# FAT93.net
KiCad netlist of a schematic drawn in Altium Designer
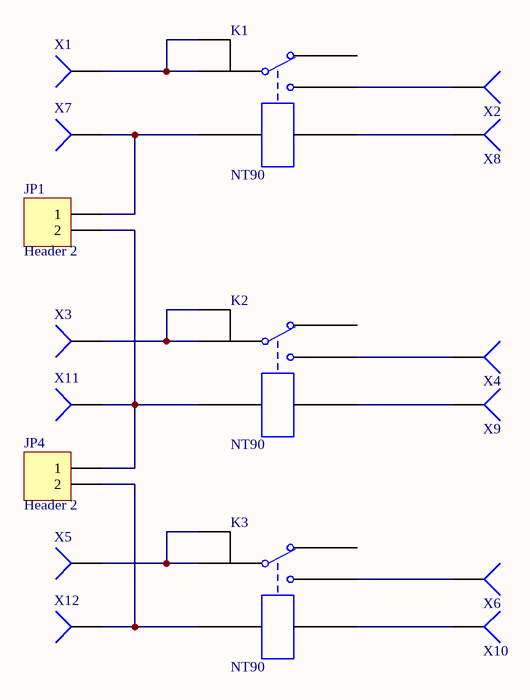
[diagram p0: FAT93.SchDoc]

(export (version "E")
  (design (tool "Eeschema 10.0.6"))
  (components
    (comp (ref "JP1")
      (value "Header 2")
      (footprint "2EDGR-5.0-2P")
      (description "Header, 2-Pin")
      (fields (field (name "MANUFACTURER") "Generic Components") (field (name "PUBLISHER") "Altium Limited"))
      (libsource (lib "Miscellaneous Connectors") (part "Header 2"))
    )
    (comp (ref "JP4")
      (value "Header 2")
      (footprint "2EDGR-5.0-2P")
      (description "Header, 2-Pin")
      (fields (field (name "MANUFACTURER") "Generic Components") (field (name "PUBLISHER") "Altium Limited"))
      (libsource (lib "Miscellaneous Connectors") (part "Header 2"))
    )
    (comp (ref "K1")
      (value "NT90")
      (footprint "NT90")
      (description "Single-Pole Dual-Throw Relay")
      (fields (field (name "MANUFACTURER") "Generic Components") (field (name "PUBLISHER") "Altium Limited"))
      (libsource (lib "PAL") (part "NT90"))
    )
    (comp (ref "K2")
      (value "NT90")
      (footprint "NT90")
      (description "Single-Pole Dual-Throw Relay")
      (fields (field (name "MANUFACTURER") "Generic Components") (field (name "PUBLISHER") "Altium Limited"))
      (libsource (lib "PAL") (part "NT90"))
    )
    (comp (ref "K3")
      (value "NT90")
      (footprint "NT90")
      (description "Single-Pole Dual-Throw Relay")
      (fields (field (name "MANUFACTURER") "Generic Components") (field (name "PUBLISHER") "Altium Limited"))
      (libsource (lib "PAL") (part "NT90"))
    )
    (comp (ref "X1")
      (value "Socket")
      (footprint "k13-4-9")
      (fields (field (name "MANUFACTURER") "Generic Components") (field (name "PUBLISHER") "Altium Limited"))
      (libsource (lib "Miscellaneous Connectors") (part "Socket"))
    )
    (comp (ref "X2")
      (value "Socket")
      (footprint "k13-4-9")
      (fields (field (name "MANUFACTURER") "Generic Components") (field (name "PUBLISHER") "Altium Limited"))
      (libsource (lib "Miscellaneous Connectors") (part "Socket"))
    )
    (comp (ref "X3")
      (value "Socket")
      (footprint "k13-4-9")
      (fields (field (name "MANUFACTURER") "Generic Components") (field (name "PUBLISHER") "Altium Limited"))
      (libsource (lib "Miscellaneous Connectors") (part "Socket"))
    )
    (comp (ref "X4")
      (value "Socket")
      (footprint "k13-4-9")
      (fields (field (name "MANUFACTURER") "Generic Components") (field (name "PUBLISHER") "Altium Limited"))
      (libsource (lib "Miscellaneous Connectors") (part "Socket"))
    )
    (comp (ref "X5")
      (value "Socket")
      (footprint "k13-4-9")
      (fields (field (name "MANUFACTURER") "Generic Components") (field (name "PUBLISHER") "Altium Limited"))
      (libsource (lib "Miscellaneous Connectors") (part "Socket"))
    )
    (comp (ref "X6")
      (value "Socket")
      (footprint "k13-4-9")
      (fields (field (name "MANUFACTURER") "Generic Components") (field (name "PUBLISHER") "Altium Limited"))
      (libsource (lib "Miscellaneous Connectors") (part "Socket"))
    )
    (comp (ref "X7")
      (value "Socket")
      (footprint "DJ610A-4.8")
      (fields (field (name "MANUFACTURER") "Generic Components") (field (name "PUBLISHER") "Altium Limited"))
      (libsource (lib "Miscellaneous Connectors") (part "Socket"))
    )
    (comp (ref "X8")
      (value "Socket")
      (footprint "DJ610A-4.8")
      (fields (field (name "MANUFACTURER") "Generic Components") (field (name "PUBLISHER") "Altium Limited"))
      (libsource (lib "Miscellaneous Connectors") (part "Socket"))
    )
    (comp (ref "X9")
      (value "Socket")
      (footprint "DJ610A-4.8")
      (fields (field (name "MANUFACTURER") "Generic Components") (field (name "PUBLISHER") "Altium Limited"))
      (libsource (lib "Miscellaneous Connectors") (part "Socket"))
    )
    (comp (ref "X10")
      (value "Socket")
      (footprint "DJ610A-4.8")
      (fields (field (name "MANUFACTURER") "Generic Components") (field (name "PUBLISHER") "Altium Limited"))
      (libsource (lib "Miscellaneous Connectors") (part "Socket"))
    )
    (comp (ref "X11")
      (value "Socket")
      (footprint "DJ610A-4.8")
      (fields (field (name "MANUFACTURER") "Generic Components") (field (name "PUBLISHER") "Altium Limited"))
      (libsource (lib "Miscellaneous Connectors") (part "Socket"))
    )
    (comp (ref "X12")
      (value "Socket")
      (footprint "DJ610A-4.8")
      (fields (field (name "MANUFACTURER") "Generic Components") (field (name "PUBLISHER") "Altium Limited"))
      (libsource (lib "Miscellaneous Connectors") (part "Socket"))
    )
  )
  (nets
    (net (code "1") (name "Net-(JP1-Pad1)") (class "Default")
      (node (ref "JP1") (pin "1") (pinfunction "1_1") (pintype "passive"))
      (node (ref "K1") (pin "4") (pinfunction "4_4") (pintype "passive"))
      (node (ref "X7") (pin "1") (pinfunction "1_1") (pintype "passive"))
    )
    (net (code "2") (name "Net-(JP1-Pad2)") (class "Default")
      (node (ref "JP1") (pin "2") (pinfunction "2_2") (pintype "passive"))
      (node (ref "JP4") (pin "1") (pinfunction "1_1") (pintype "passive"))
      (node (ref "K2") (pin "4") (pinfunction "4_4") (pintype "passive"))
      (node (ref "X11") (pin "1") (pinfunction "1_1") (pintype "passive"))
    )
    (net (code "3") (name "Net-(JP4-Pad2)") (class "Default")
      (node (ref "JP4") (pin "2") (pinfunction "2_2") (pintype "passive"))
      (node (ref "K3") (pin "4") (pinfunction "4_4") (pintype "passive"))
      (node (ref "X12") (pin "1") (pinfunction "1_1") (pintype "passive"))
    )
    (net (code "4") (name "Net-(K1-Pad1)") (class "Default")
      (node (ref "K1") (pin "1") (pinfunction "1_1") (pintype "passive"))
      (node (ref "K1") (pin "6") (pinfunction "6_6") (pintype "passive"))
      (node (ref "X1") (pin "1") (pinfunction "1_1") (pintype "passive"))
    )
    (net (code "5") (name "Net-(K1-Pad3)") (class "Default")
      (node (ref "K1") (pin "3") (pinfunction "3_3") (pintype "passive"))
      (node (ref "X2") (pin "1") (pinfunction "1_1") (pintype "passive"))
    )
    (net (code "6") (name "Net-(K1-Pad5)") (class "Default")
      (node (ref "K1") (pin "5") (pinfunction "5_5") (pintype "passive"))
      (node (ref "X8") (pin "1") (pinfunction "1_1") (pintype "passive"))
    )
    (net (code "7") (name "Net-(K2-Pad1)") (class "Default")
      (node (ref "K2") (pin "1") (pinfunction "1_1") (pintype "passive"))
      (node (ref "K2") (pin "6") (pinfunction "6_6") (pintype "passive"))
      (node (ref "X3") (pin "1") (pinfunction "1_1") (pintype "passive"))
    )
    (net (code "8") (name "Net-(K2-Pad3)") (class "Default")
      (node (ref "K2") (pin "3") (pinfunction "3_3") (pintype "passive"))
      (node (ref "X4") (pin "1") (pinfunction "1_1") (pintype "passive"))
    )
    (net (code "9") (name "Net-(K2-Pad5)") (class "Default")
      (node (ref "K2") (pin "5") (pinfunction "5_5") (pintype "passive"))
      (node (ref "X9") (pin "1") (pinfunction "1_1") (pintype "passive"))
    )
    (net (code "10") (name "Net-(K3-Pad1)") (class "Default")
      (node (ref "K3") (pin "1") (pinfunction "1_1") (pintype "passive"))
      (node (ref "K3") (pin "6") (pinfunction "6_6") (pintype "passive"))
      (node (ref "X5") (pin "1") (pinfunction "1_1") (pintype "passive"))
    )
    (net (code "11") (name "Net-(K3-Pad3)") (class "Default")
      (node (ref "K3") (pin "3") (pinfunction "3_3") (pintype "passive"))
      (node (ref "X6") (pin "1") (pinfunction "1_1") (pintype "passive"))
    )
    (net (code "12") (name "Net-(K3-Pad5)") (class "Default")
      (node (ref "K3") (pin "5") (pinfunction "5_5") (pintype "passive"))
      (node (ref "X10") (pin "1") (pinfunction "1_1") (pintype "passive"))
    )
    (net (code "13") (name "unconnected-(K1-Pad2)") (class "Default")
      (node (ref "K1") (pin "2") (pinfunction "2_2") (pintype "passive"))
    )
    (net (code "14") (name "unconnected-(K2-Pad2)") (class "Default")
      (node (ref "K2") (pin "2") (pinfunction "2_2") (pintype "passive"))
    )
    (net (code "15") (name "unconnected-(K3-Pad2)") (class "Default")
      (node (ref "K3") (pin "2") (pinfunction "2_2") (pintype "passive"))
    )
  )
)
